# IO.net
KiCad netlist of a schematic drawn in Altium Designer
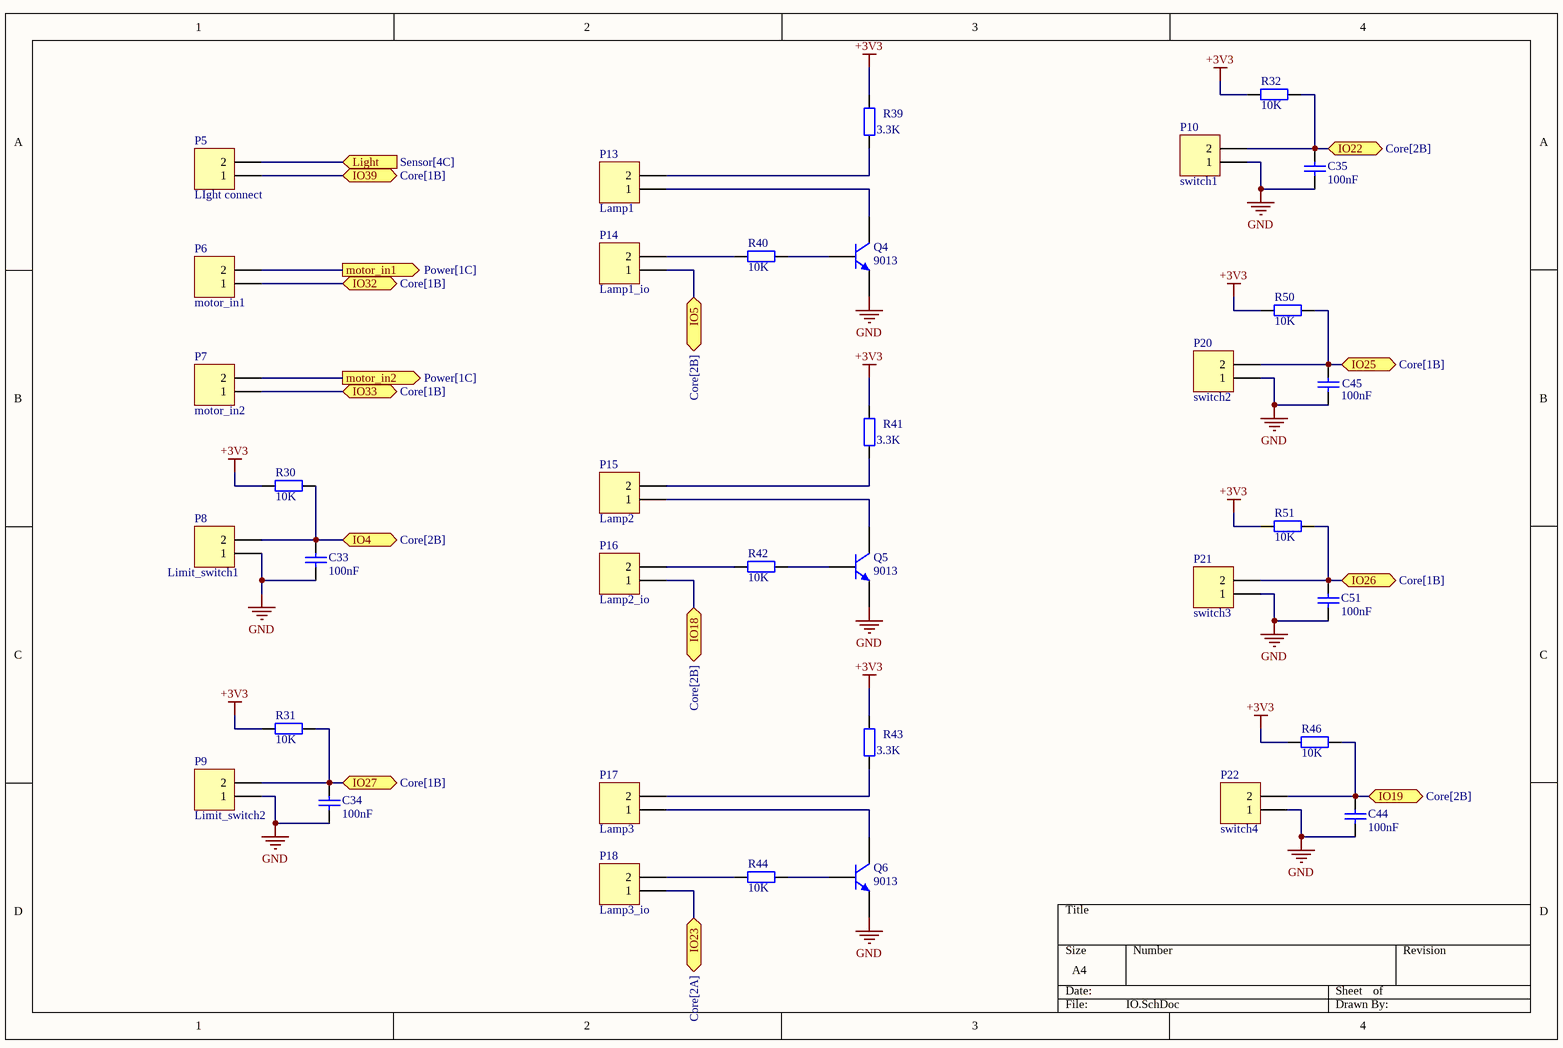
[diagram p0: IO.SchDoc]

(export (version "E")
  (design (tool "Eeschema 10.0.6"))
  (components
    (comp (ref "C33")
      (value "100nF")
      (footprint "6-0805_N")
      (description "Capacitor")
      (fields (field (name "Comment") "Cap") (field (name "PUBLISHER") "Altium Limited"))
      (libsource (lib "Miscellaneous Devices") (part "Cap"))
    )
    (comp (ref "C34")
      (value "100nF")
      (footprint "6-0805_N")
      (description "Capacitor")
      (fields (field (name "Comment") "Cap") (field (name "PUBLISHER") "Altium Limited"))
      (libsource (lib "Miscellaneous Devices") (part "Cap"))
    )
    (comp (ref "C35")
      (value "100nF")
      (footprint "6-0805_N")
      (description "Capacitor")
      (fields (field (name "Comment") "Cap") (field (name "PUBLISHER") "Altium Limited"))
      (libsource (lib "Miscellaneous Devices") (part "Cap"))
    )
    (comp (ref "C44")
      (value "100nF")
      (footprint "6-0805_N")
      (description "Capacitor")
      (fields (field (name "Comment") "Cap") (field (name "PUBLISHER") "Altium Limited"))
      (libsource (lib "Miscellaneous Devices") (part "Cap"))
    )
    (comp (ref "C45")
      (value "100nF")
      (footprint "6-0805_N")
      (description "Capacitor")
      (fields (field (name "Comment") "Cap") (field (name "PUBLISHER") "Altium Limited"))
      (libsource (lib "Miscellaneous Devices") (part "Cap"))
    )
    (comp (ref "C51")
      (value "100nF")
      (footprint "6-0805_N")
      (description "Capacitor")
      (fields (field (name "Comment") "Cap") (field (name "PUBLISHER") "Altium Limited"))
      (libsource (lib "Miscellaneous Devices") (part "Cap"))
    )
    (comp (ref "P5")
      (value "LIght connect")
      (footprint "HDR1X2")
      (description "Header, 2-Pin")
      (fields (field (name "PUBLISHER") "Altium Limited"))
      (libsource (lib "Miscellaneous Connectors") (part "Header 2"))
    )
    (comp (ref "P6")
      (value "motor_in1")
      (footprint "HDR1X2")
      (description "Header, 2-Pin")
      (fields (field (name "PUBLISHER") "Altium Limited"))
      (libsource (lib "Miscellaneous Connectors") (part "Header 2"))
    )
    (comp (ref "P7")
      (value "motor_in2")
      (footprint "HDR1X2")
      (description "Header, 2-Pin")
      (fields (field (name "PUBLISHER") "Altium Limited"))
      (libsource (lib "Miscellaneous Connectors") (part "Header 2"))
    )
    (comp (ref "P8")
      (value "Limit_switch1")
      (footprint "HDR1X2")
      (description "Header, 2-Pin")
      (fields (field (name "PUBLISHER") "Altium Limited"))
      (libsource (lib "Miscellaneous Connectors") (part "Header 2"))
    )
    (comp (ref "P9")
      (value "Limit_switch2")
      (footprint "HDR1X2")
      (description "Header, 2-Pin")
      (fields (field (name "PUBLISHER") "Altium Limited"))
      (libsource (lib "Miscellaneous Connectors") (part "Header 2"))
    )
    (comp (ref "P10")
      (value "switch1")
      (footprint "HDR1X2")
      (description "Header, 2-Pin")
      (fields (field (name "PUBLISHER") "Altium Limited"))
      (libsource (lib "Miscellaneous Connectors") (part "Header 2"))
    )
    (comp (ref "P13")
      (value "Lamp1")
      (footprint "HDR1X2")
      (description "Header, 2-Pin")
      (fields (field (name "PUBLISHER") "Altium Limited"))
      (libsource (lib "Miscellaneous Connectors") (part "Header 2"))
    )
    (comp (ref "P14")
      (value "Lamp1_io")
      (footprint "HDR1X2")
      (description "Header, 2-Pin")
      (fields (field (name "PUBLISHER") "Altium Limited"))
      (libsource (lib "Miscellaneous Connectors") (part "Header 2"))
    )
    (comp (ref "P15")
      (value "Lamp2")
      (footprint "HDR1X2")
      (description "Header, 2-Pin")
      (fields (field (name "PUBLISHER") "Altium Limited"))
      (libsource (lib "Miscellaneous Connectors") (part "Header 2"))
    )
    (comp (ref "P16")
      (value "Lamp2_io")
      (footprint "HDR1X2")
      (description "Header, 2-Pin")
      (fields (field (name "PUBLISHER") "Altium Limited"))
      (libsource (lib "Miscellaneous Connectors") (part "Header 2"))
    )
    (comp (ref "P17")
      (value "Lamp3")
      (footprint "HDR1X2")
      (description "Header, 2-Pin")
      (fields (field (name "PUBLISHER") "Altium Limited"))
      (libsource (lib "Miscellaneous Connectors") (part "Header 2"))
    )
    (comp (ref "P18")
      (value "Lamp3_io")
      (footprint "HDR1X2")
      (description "Header, 2-Pin")
      (fields (field (name "PUBLISHER") "Altium Limited"))
      (libsource (lib "Miscellaneous Connectors") (part "Header 2"))
    )
    (comp (ref "P20")
      (value "switch2")
      (footprint "HDR1X2")
      (description "Header, 2-Pin")
      (fields (field (name "PUBLISHER") "Altium Limited"))
      (libsource (lib "Miscellaneous Connectors") (part "Header 2"))
    )
    (comp (ref "P21")
      (value "switch3")
      (footprint "HDR1X2")
      (description "Header, 2-Pin")
      (fields (field (name "PUBLISHER") "Altium Limited"))
      (libsource (lib "Miscellaneous Connectors") (part "Header 2"))
    )
    (comp (ref "P22")
      (value "switch4")
      (footprint "HDR1X2")
      (description "Header, 2-Pin")
      (fields (field (name "PUBLISHER") "Altium Limited"))
      (libsource (lib "Miscellaneous Connectors") (part "Header 2"))
    )
    (comp (ref "Q4")
      (value "9013")
      (footprint "SOT-23-3_L2.9-W1.3-P1.90-LS2.4-BR")
      (description "NPN General Purpose Amplifier")
      (fields (field (name "PUBLISHER") "Altium Limited"))
      (libsource (lib "Miscellaneous Devices") (part "2N3904"))
    )
    (comp (ref "Q5")
      (value "9013")
      (footprint "SOT-23-3_L2.9-W1.3-P1.90-LS2.4-BR")
      (description "NPN General Purpose Amplifier")
      (fields (field (name "PUBLISHER") "Altium Limited"))
      (libsource (lib "Miscellaneous Devices") (part "2N3904"))
    )
    (comp (ref "Q6")
      (value "9013")
      (footprint "SOT-23-3_L2.9-W1.3-P1.90-LS2.4-BR")
      (description "NPN General Purpose Amplifier")
      (fields (field (name "PUBLISHER") "Altium Limited"))
      (libsource (lib "Miscellaneous Devices") (part "2N3904"))
    )
    (comp (ref "R30")
      (value "10K")
      (footprint "6-0805_N")
      (description "Resistor")
      (fields (field (name "Comment") "Res2") (field (name "PUBLISHER") "Altium Limited"))
      (libsource (lib "Miscellaneous Devices") (part "Res2"))
    )
    (comp (ref "R31")
      (value "10K")
      (footprint "6-0805_N")
      (description "Resistor")
      (fields (field (name "Comment") "Res2") (field (name "PUBLISHER") "Altium Limited"))
      (libsource (lib "Miscellaneous Devices") (part "Res2"))
    )
    (comp (ref "R32")
      (value "10K")
      (footprint "6-0805_N")
      (description "Resistor")
      (fields (field (name "Comment") "Res2") (field (name "PUBLISHER") "Altium Limited"))
      (libsource (lib "Miscellaneous Devices") (part "Res2"))
    )
    (comp (ref "R39")
      (value "3.3K")
      (footprint "6-0805_N")
      (description "Resistor")
      (fields (field (name "Comment") "Res2") (field (name "PUBLISHER") "Altium Limited"))
      (libsource (lib "") (part "Res2_1"))
    )
    (comp (ref "R40")
      (value "10K")
      (footprint "6-0805_N")
      (description "Resistor")
      (fields (field (name "Comment") "Res2") (field (name "PUBLISHER") "Altium Limited"))
      (libsource (lib "Miscellaneous Devices") (part "Res2"))
    )
    (comp (ref "R41")
      (value "3.3K")
      (footprint "6-0805_N")
      (description "Resistor")
      (fields (field (name "Comment") "Res2") (field (name "PUBLISHER") "Altium Limited"))
      (libsource (lib "") (part "Res2_1"))
    )
    (comp (ref "R42")
      (value "10K")
      (footprint "6-0805_N")
      (description "Resistor")
      (fields (field (name "Comment") "Res2") (field (name "PUBLISHER") "Altium Limited"))
      (libsource (lib "Miscellaneous Devices") (part "Res2"))
    )
    (comp (ref "R43")
      (value "3.3K")
      (footprint "6-0805_N")
      (description "Resistor")
      (fields (field (name "Comment") "Res2") (field (name "PUBLISHER") "Altium Limited"))
      (libsource (lib "") (part "Res2_1"))
    )
    (comp (ref "R44")
      (value "10K")
      (footprint "6-0805_N")
      (description "Resistor")
      (fields (field (name "Comment") "Res2") (field (name "PUBLISHER") "Altium Limited"))
      (libsource (lib "Miscellaneous Devices") (part "Res2"))
    )
    (comp (ref "R46")
      (value "10K")
      (footprint "6-0805_N")
      (description "Resistor")
      (fields (field (name "Comment") "Res2") (field (name "PUBLISHER") "Altium Limited"))
      (libsource (lib "Miscellaneous Devices") (part "Res2"))
    )
    (comp (ref "R50")
      (value "10K")
      (footprint "6-0805_N")
      (description "Resistor")
      (fields (field (name "Comment") "Res2") (field (name "PUBLISHER") "Altium Limited"))
      (libsource (lib "Miscellaneous Devices") (part "Res2"))
    )
    (comp (ref "R51")
      (value "10K")
      (footprint "6-0805_N")
      (description "Resistor")
      (fields (field (name "Comment") "Res2") (field (name "PUBLISHER") "Altium Limited"))
      (libsource (lib "Miscellaneous Devices") (part "Res2"))
    )
  )
  (nets
    (net (code "1") (name "+3V3") (class "Default")
      (node (ref "R30") (pin "1") (pinfunction "1_1") (pintype "passive"))
      (node (ref "R31") (pin "1") (pinfunction "1_1") (pintype "passive"))
      (node (ref "R32") (pin "1") (pinfunction "1_1") (pintype "passive"))
      (node (ref "R39") (pin "1") (pinfunction "1_1") (pintype "passive"))
      (node (ref "R41") (pin "1") (pinfunction "1_1") (pintype "passive"))
      (node (ref "R43") (pin "1") (pinfunction "1_1") (pintype "passive"))
      (node (ref "R46") (pin "1") (pinfunction "1_1") (pintype "passive"))
      (node (ref "R50") (pin "1") (pinfunction "1_1") (pintype "passive"))
      (node (ref "R51") (pin "1") (pinfunction "1_1") (pintype "passive"))
    )
    (net (code "2") (name "/IO4") (class "Default")
      (node (ref "C33") (pin "2") (pinfunction "2_2") (pintype "passive"))
      (node (ref "P8") (pin "2") (pinfunction "2_2") (pintype "passive"))
      (node (ref "R30") (pin "2") (pinfunction "2_2") (pintype "passive"))
    )
    (net (code "3") (name "/IO5") (class "Default")
      (node (ref "P14") (pin "1") (pinfunction "1_1") (pintype "passive"))
    )
    (net (code "4") (name "/IO18") (class "Default")
      (node (ref "P16") (pin "1") (pinfunction "1_1") (pintype "passive"))
    )
    (net (code "5") (name "/IO19") (class "Default")
      (node (ref "C44") (pin "2") (pinfunction "2_2") (pintype "passive"))
      (node (ref "P22") (pin "2") (pinfunction "2_2") (pintype "passive"))
      (node (ref "R46") (pin "2") (pinfunction "2_2") (pintype "passive"))
    )
    (net (code "6") (name "/IO22") (class "Default")
      (node (ref "C35") (pin "2") (pinfunction "2_2") (pintype "passive"))
      (node (ref "P10") (pin "2") (pinfunction "2_2") (pintype "passive"))
      (node (ref "R32") (pin "2") (pinfunction "2_2") (pintype "passive"))
    )
    (net (code "7") (name "/IO23") (class "Default")
      (node (ref "P18") (pin "1") (pinfunction "1_1") (pintype "passive"))
    )
    (net (code "8") (name "/IO25") (class "Default")
      (node (ref "C45") (pin "2") (pinfunction "2_2") (pintype "passive"))
      (node (ref "P20") (pin "2") (pinfunction "2_2") (pintype "passive"))
      (node (ref "R50") (pin "2") (pinfunction "2_2") (pintype "passive"))
    )
    (net (code "9") (name "/IO26") (class "Default")
      (node (ref "C51") (pin "2") (pinfunction "2_2") (pintype "passive"))
      (node (ref "P21") (pin "2") (pinfunction "2_2") (pintype "passive"))
      (node (ref "R51") (pin "2") (pinfunction "2_2") (pintype "passive"))
    )
    (net (code "10") (name "/IO27") (class "Default")
      (node (ref "C34") (pin "2") (pinfunction "2_2") (pintype "passive"))
      (node (ref "P9") (pin "2") (pinfunction "2_2") (pintype "passive"))
      (node (ref "R31") (pin "2") (pinfunction "2_2") (pintype "passive"))
    )
    (net (code "11") (name "/IO32") (class "Default")
      (node (ref "P6") (pin "1") (pinfunction "1_1") (pintype "passive"))
    )
    (net (code "12") (name "/IO33") (class "Default")
      (node (ref "P7") (pin "1") (pinfunction "1_1") (pintype "passive"))
    )
    (net (code "13") (name "/IO39") (class "Default")
      (node (ref "P5") (pin "1") (pinfunction "1_1") (pintype "passive"))
    )
    (net (code "14") (name "/Light") (class "Default")
      (node (ref "P5") (pin "2") (pinfunction "2_2") (pintype "passive"))
    )
    (net (code "15") (name "/motor_in1") (class "Default")
      (node (ref "P6") (pin "2") (pinfunction "2_2") (pintype "passive"))
    )
    (net (code "16") (name "/motor_in2") (class "Default")
      (node (ref "P7") (pin "2") (pinfunction "2_2") (pintype "passive"))
    )
    (net (code "17") (name "GND") (class "Default")
      (node (ref "C33") (pin "1") (pinfunction "1_1") (pintype "passive"))
      (node (ref "C34") (pin "1") (pinfunction "1_1") (pintype "passive"))
      (node (ref "C35") (pin "1") (pinfunction "1_1") (pintype "passive"))
      (node (ref "C44") (pin "1") (pinfunction "1_1") (pintype "passive"))
      (node (ref "C45") (pin "1") (pinfunction "1_1") (pintype "passive"))
      (node (ref "C51") (pin "1") (pinfunction "1_1") (pintype "passive"))
      (node (ref "P10") (pin "1") (pinfunction "1_1") (pintype "passive"))
      (node (ref "P20") (pin "1") (pinfunction "1_1") (pintype "passive"))
      (node (ref "P21") (pin "1") (pinfunction "1_1") (pintype "passive"))
      (node (ref "P22") (pin "1") (pinfunction "1_1") (pintype "passive"))
      (node (ref "P8") (pin "1") (pinfunction "1_1") (pintype "passive"))
      (node (ref "P9") (pin "1") (pinfunction "1_1") (pintype "passive"))
      (node (ref "Q4") (pin "1") (pinfunction "E_1") (pintype "passive"))
      (node (ref "Q5") (pin "1") (pinfunction "E_1") (pintype "passive"))
      (node (ref "Q6") (pin "1") (pinfunction "E_1") (pintype "passive"))
    )
    (net (code "18") (name "Net-(P13-Pad2)") (class "Default")
      (node (ref "P13") (pin "2") (pinfunction "2_2") (pintype "passive"))
      (node (ref "R39") (pin "2") (pinfunction "2_2") (pintype "passive"))
    )
    (net (code "19") (name "Net-(P14-Pad2)") (class "Default")
      (node (ref "P14") (pin "2") (pinfunction "2_2") (pintype "passive"))
      (node (ref "R40") (pin "1") (pinfunction "1_1") (pintype "passive"))
    )
    (net (code "20") (name "Net-(P15-Pad2)") (class "Default")
      (node (ref "P15") (pin "2") (pinfunction "2_2") (pintype "passive"))
      (node (ref "R41") (pin "2") (pinfunction "2_2") (pintype "passive"))
    )
    (net (code "21") (name "Net-(P16-Pad2)") (class "Default")
      (node (ref "P16") (pin "2") (pinfunction "2_2") (pintype "passive"))
      (node (ref "R42") (pin "1") (pinfunction "1_1") (pintype "passive"))
    )
    (net (code "22") (name "Net-(P17-Pad2)") (class "Default")
      (node (ref "P17") (pin "2") (pinfunction "2_2") (pintype "passive"))
      (node (ref "R43") (pin "2") (pinfunction "2_2") (pintype "passive"))
    )
    (net (code "23") (name "Net-(P18-Pad2)") (class "Default")
      (node (ref "P18") (pin "2") (pinfunction "2_2") (pintype "passive"))
      (node (ref "R44") (pin "1") (pinfunction "1_1") (pintype "passive"))
    )
    (net (code "24") (name "Net-(Q4-B)") (class "Default")
      (node (ref "Q4") (pin "2") (pinfunction "B_2") (pintype "passive"))
      (node (ref "R40") (pin "2") (pinfunction "2_2") (pintype "passive"))
    )
    (net (code "25") (name "Net-(Q4-C)") (class "Default")
      (node (ref "P13") (pin "1") (pinfunction "1_1") (pintype "passive"))
      (node (ref "Q4") (pin "3") (pinfunction "C_3") (pintype "passive"))
    )
    (net (code "26") (name "Net-(Q5-B)") (class "Default")
      (node (ref "Q5") (pin "2") (pinfunction "B_2") (pintype "passive"))
      (node (ref "R42") (pin "2") (pinfunction "2_2") (pintype "passive"))
    )
    (net (code "27") (name "Net-(Q5-C)") (class "Default")
      (node (ref "P15") (pin "1") (pinfunction "1_1") (pintype "passive"))
      (node (ref "Q5") (pin "3") (pinfunction "C_3") (pintype "passive"))
    )
    (net (code "28") (name "Net-(Q6-B)") (class "Default")
      (node (ref "Q6") (pin "2") (pinfunction "B_2") (pintype "passive"))
      (node (ref "R44") (pin "2") (pinfunction "2_2") (pintype "passive"))
    )
    (net (code "29") (name "Net-(Q6-C)") (class "Default")
      (node (ref "P17") (pin "1") (pinfunction "1_1") (pintype "passive"))
      (node (ref "Q6") (pin "3") (pinfunction "C_3") (pintype "passive"))
    )
  )
)
